# 301_FrameUSB.net
KiCad netlist of a schematic drawn in Altium Designer
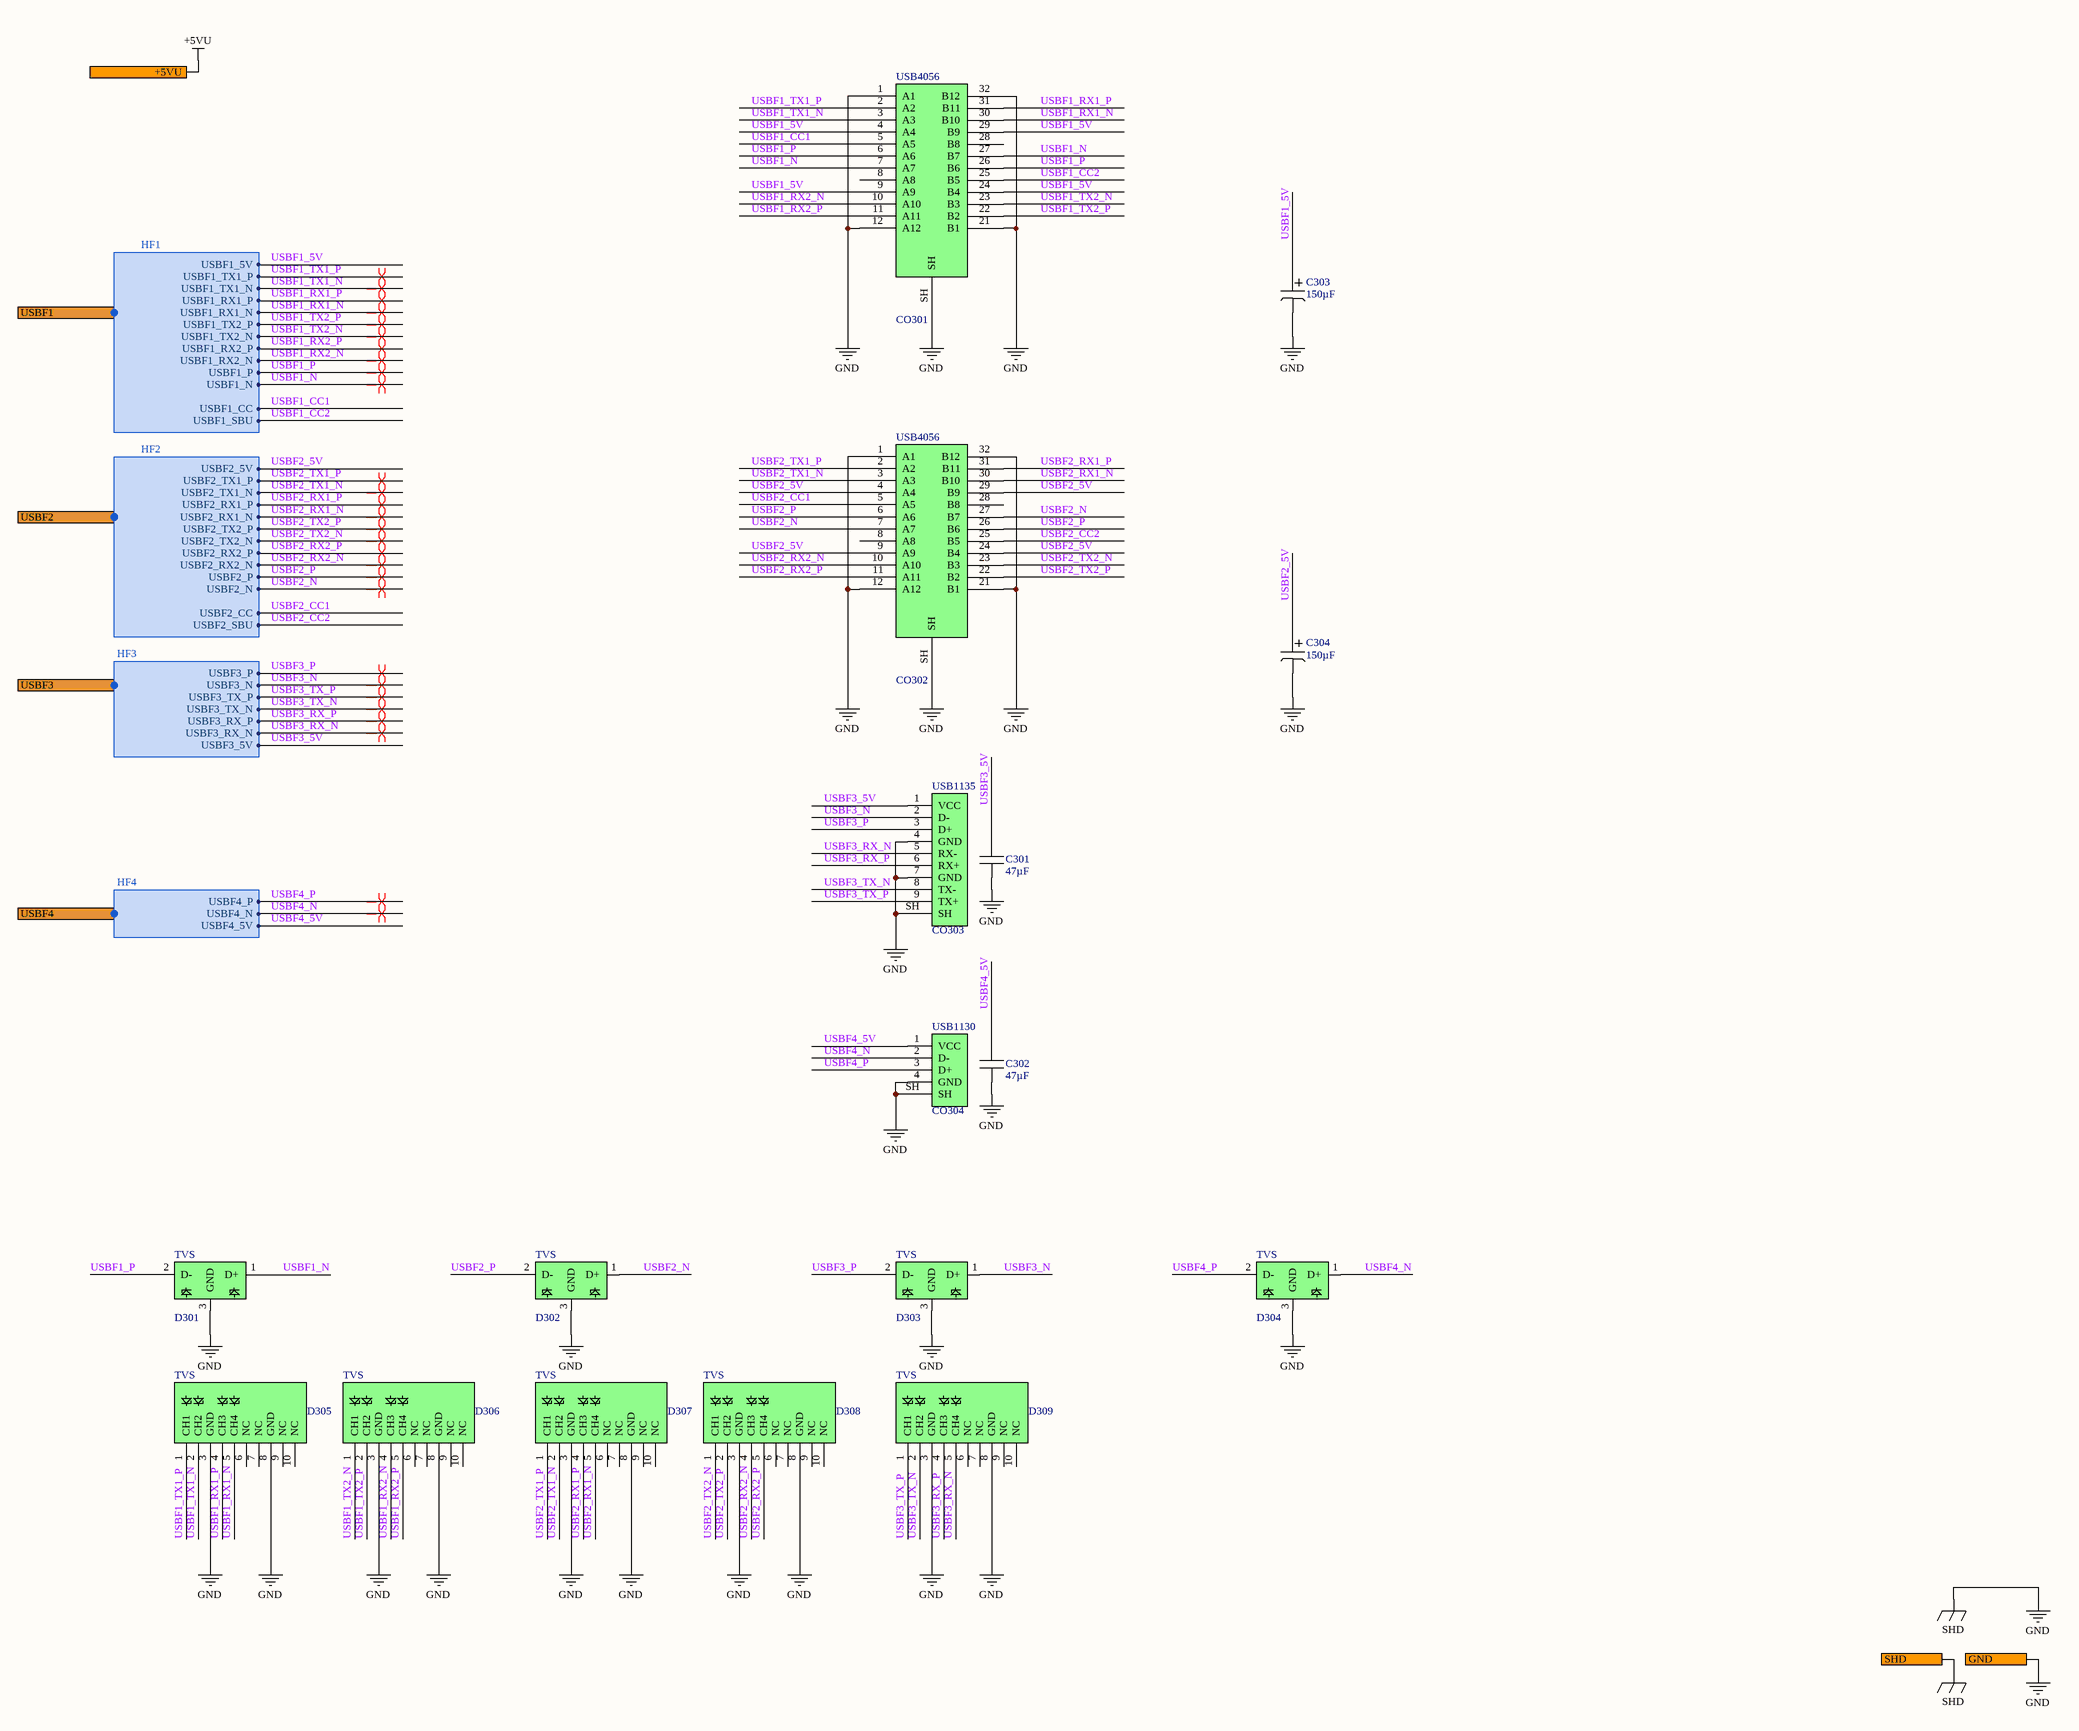
[diagram p0: 301_FrameUSB.SchDoc]

(export (version "E")
  (design (tool "Eeschema 10.0.6"))
  (components
    (comp (ref "C301")
      (value "47µF")
      (footprint "C1210")
      (description "47µF 16V 20% X5R")
      (fields
        (field (name "REFVAL") "47µF")
        (field (name "PART NUMBER") "CA0007")
        (field (name "MANFACTPART") "EMK325ABJ476MM8P")
      )
      (libsource (lib "GTS_Database") (part "C"))
    )
    (comp (ref "C302")
      (value "47µF")
      (footprint "C1210")
      (description "47µF 16V 20% X5R")
      (fields
        (field (name "REFVAL") "47µF")
        (field (name "PART NUMBER") "CA0007")
        (field (name "MANFACTPART") "EMK325ABJ476MM8P")
      )
      (libsource (lib "GTS_Database") (part "C"))
    )
    (comp (ref "C303")
      (value "150µF")
      (footprint "RL_10_5_12.5")
      (description "150µF 50V 20% 363mA")
      (fields
        (field (name "REFVAL") "150µF")
        (field (name "PART NUMBER") "CA0043")
        (field (name "MANFACTPART") "860010675016")
      )
      (libsource (lib "GTS_Database") (part "C+"))
    )
    (comp (ref "C304")
      (value "150µF")
      (footprint "RL_10_5_12.5")
      (description "150µF 50V 20% 363mA")
      (fields
        (field (name "REFVAL") "150µF")
        (field (name "PART NUMBER") "CA0043")
        (field (name "MANFACTPART") "860010675016")
      )
      (libsource (lib "GTS_Database") (part "C+"))
    )
    (comp (ref "CO301")
      (value "USB4056")
      (footprint "USB4056-03-A")
      (description "USB C connector Receptacle Horizontal")
      (fields
        (field (name "REFVAL") "USB4056")
        (field (name "PART NUMBER") "CO0030")
        (field (name "MANFACTPART") "USB4056-03-A")
      )
      (libsource (lib "GTS_Database") (part "USB-CC"))
    )
    (comp (ref "CO302")
      (value "USB4056")
      (footprint "USB4056-03-A")
      (description "USB C connector Receptacle Horizontal")
      (fields
        (field (name "REFVAL") "USB4056")
        (field (name "PART NUMBER") "CO0030")
        (field (name "MANFACTPART") "USB4056-03-A")
      )
      (libsource (lib "GTS_Database") (part "USB-CC"))
    )
    (comp (ref "CO303")
      (value "USB1135")
      (footprint "USB1135-15-9-L-B")
      (description "USB3.0 Type A receptacle Horizontal")
      (fields
        (field (name "REFVAL") "USB1135")
        (field (name "PART NUMBER") "CO0041")
        (field (name "MANFACTPART") "USB1135-15-9-L-B")
      )
      (libsource (lib "GTS_Database") (part "USB3"))
    )
    (comp (ref "CO304")
      (value "USB1130")
      (footprint "USB1130-15-A")
      (description "USB2.0 Type A receptacle Horizontal")
      (fields
        (field (name "REFVAL") "USB1130")
        (field (name "PART NUMBER") "CO0040")
        (field (name "MANFACTPART") "USB1130-15-A")
      )
      (libsource (lib "GTS_Database") (part "USB2"))
    )
    (comp (ref "D301")
      (value "TVS")
      (footprint "SOT-3")
      (description "USB 2 TVS Diode")
      (fields
        (field (name "REFVAL") "TVS")
        (field (name "PART NUMBER") "DI0002")
        (field (name "MANFACTPART") "TPD2EUSB30DRTR")
      )
      (libsource (lib "GTS_Database") (part "USB2TVS"))
    )
    (comp (ref "D302")
      (value "TVS")
      (footprint "SOT-3")
      (description "USB 2 TVS Diode")
      (fields
        (field (name "REFVAL") "TVS")
        (field (name "PART NUMBER") "DI0002")
        (field (name "MANFACTPART") "TPD2EUSB30DRTR")
      )
      (libsource (lib "GTS_Database") (part "USB2TVS"))
    )
    (comp (ref "D303")
      (value "TVS")
      (footprint "SOT-3")
      (description "USB 2 TVS Diode")
      (fields
        (field (name "REFVAL") "TVS")
        (field (name "PART NUMBER") "DI0002")
        (field (name "MANFACTPART") "TPD2EUSB30DRTR")
      )
      (libsource (lib "GTS_Database") (part "USB2TVS"))
    )
    (comp (ref "D304")
      (value "TVS")
      (footprint "SOT-3")
      (description "USB 2 TVS Diode")
      (fields
        (field (name "REFVAL") "TVS")
        (field (name "PART NUMBER") "DI0002")
        (field (name "MANFACTPART") "TPD2EUSB30DRTR")
      )
      (libsource (lib "GTS_Database") (part "USB2TVS"))
    )
    (comp (ref "D305")
      (value "TVS")
      (footprint "SOT-1176-1")
      (description "USB 3 TVS Diode")
      (fields
        (field (name "REFVAL") "TVS")
        (field (name "PART NUMBER") "DI0007")
        (field (name "MANFACTPART") "PUSB3FA2Z")
      )
      (libsource (lib "GTS_Database") (part "USB3TVS"))
    )
    (comp (ref "D306")
      (value "TVS")
      (footprint "SOT-1176-1")
      (description "USB 3 TVS Diode")
      (fields
        (field (name "REFVAL") "TVS")
        (field (name "PART NUMBER") "DI0007")
        (field (name "MANFACTPART") "PUSB3FA2Z")
      )
      (libsource (lib "GTS_Database") (part "USB3TVS"))
    )
    (comp (ref "D307")
      (value "TVS")
      (footprint "SOT-1176-1")
      (description "USB 3 TVS Diode")
      (fields
        (field (name "REFVAL") "TVS")
        (field (name "PART NUMBER") "DI0007")
        (field (name "MANFACTPART") "PUSB3FA2Z")
      )
      (libsource (lib "GTS_Database") (part "USB3TVS"))
    )
    (comp (ref "D308")
      (value "TVS")
      (footprint "SOT-1176-1")
      (description "USB 3 TVS Diode")
      (fields
        (field (name "REFVAL") "TVS")
        (field (name "PART NUMBER") "DI0007")
        (field (name "MANFACTPART") "PUSB3FA2Z")
      )
      (libsource (lib "GTS_Database") (part "USB3TVS"))
    )
    (comp (ref "D309")
      (value "TVS")
      (footprint "SOT-1176-1")
      (description "USB 3 TVS Diode")
      (fields
        (field (name "REFVAL") "TVS")
        (field (name "PART NUMBER") "DI0007")
        (field (name "MANFACTPART") "PUSB3FA2Z")
      )
      (libsource (lib "GTS_Database") (part "USB3TVS"))
    )
  )
  (nets
    (net (code "6") (name "/USBF1_5V") (class "Default")
      (node (ref "C303") (pin "1") (pinfunction "1_1") (pintype "passive"))
      (node (ref "CO301") (pin "24") (pinfunction "B4_24") (pintype "passive"))
      (node (ref "CO301") (pin "29") (pinfunction "B9_29") (pintype "passive"))
      (node (ref "CO301") (pin "4") (pinfunction "A4_4") (pintype "passive"))
      (node (ref "CO301") (pin "9") (pinfunction "A9_9") (pintype "passive"))
    )
    (net (code "7") (name "/USBF1_CC1") (class "Default")
      (node (ref "CO301") (pin "5") (pinfunction "A5_5") (pintype "passive"))
    )
    (net (code "8") (name "/USBF1_CC2") (class "Default")
      (node (ref "CO301") (pin "25") (pinfunction "B5_25") (pintype "passive"))
    )
    (net (code "9") (name "/USBF1_N") (class "Default")
      (node (ref "CO301") (pin "27") (pinfunction "B7_27") (pintype "passive"))
      (node (ref "CO301") (pin "7") (pinfunction "A7_7") (pintype "passive"))
      (node (ref "D301") (pin "1") (pinfunction "D+_1") (pintype "passive"))
    )
    (net (code "10") (name "/USBF1_P") (class "Default")
      (node (ref "CO301") (pin "26") (pinfunction "B6_26") (pintype "passive"))
      (node (ref "CO301") (pin "6") (pinfunction "A6_6") (pintype "passive"))
      (node (ref "D301") (pin "2") (pinfunction "D-_2") (pintype "passive"))
    )
    (net (code "11") (name "/USBF1_RX1_N") (class "Default")
      (node (ref "CO301") (pin "30") (pinfunction "B10_30") (pintype "passive"))
      (node (ref "D305") (pin "5") (pinfunction "CH4_5") (pintype "passive"))
    )
    (net (code "12") (name "/USBF1_RX1_P") (class "Default")
      (node (ref "CO301") (pin "31") (pinfunction "B11_31") (pintype "passive"))
      (node (ref "D305") (pin "4") (pinfunction "CH3_4") (pintype "passive"))
    )
    (net (code "13") (name "/USBF1_RX2_N") (class "Default")
      (node (ref "CO301") (pin "10") (pinfunction "A10_10") (pintype "passive"))
      (node (ref "D306") (pin "4") (pinfunction "CH3_4") (pintype "passive"))
    )
    (net (code "14") (name "/USBF1_RX2_P") (class "Default")
      (node (ref "CO301") (pin "11") (pinfunction "A11_11") (pintype "passive"))
      (node (ref "D306") (pin "5") (pinfunction "CH4_5") (pintype "passive"))
    )
    (net (code "15") (name "/USBF1_TX1_N") (class "Default")
      (node (ref "CO301") (pin "3") (pinfunction "A3_3") (pintype "passive"))
      (node (ref "D305") (pin "2") (pinfunction "CH2_2") (pintype "passive"))
    )
    (net (code "16") (name "/USBF1_TX1_P") (class "Default")
      (node (ref "CO301") (pin "2") (pinfunction "A2_2") (pintype "passive"))
      (node (ref "D305") (pin "1") (pinfunction "CH1_1") (pintype "passive"))
    )
    (net (code "17") (name "/USBF1_TX2_N") (class "Default")
      (node (ref "CO301") (pin "23") (pinfunction "B3_23") (pintype "passive"))
      (node (ref "D306") (pin "1") (pinfunction "CH1_1") (pintype "passive"))
    )
    (net (code "18") (name "/USBF1_TX2_P") (class "Default")
      (node (ref "CO301") (pin "22") (pinfunction "B2_22") (pintype "passive"))
      (node (ref "D306") (pin "2") (pinfunction "CH2_2") (pintype "passive"))
    )
    (net (code "19") (name "/USBF2_5V") (class "Default")
      (node (ref "C304") (pin "1") (pinfunction "1_1") (pintype "passive"))
      (node (ref "CO302") (pin "24") (pinfunction "B4_24") (pintype "passive"))
      (node (ref "CO302") (pin "29") (pinfunction "B9_29") (pintype "passive"))
      (node (ref "CO302") (pin "4") (pinfunction "A4_4") (pintype "passive"))
      (node (ref "CO302") (pin "9") (pinfunction "A9_9") (pintype "passive"))
    )
    (net (code "20") (name "/USBF2_CC1") (class "Default")
      (node (ref "CO302") (pin "5") (pinfunction "A5_5") (pintype "passive"))
    )
    (net (code "21") (name "/USBF2_CC2") (class "Default")
      (node (ref "CO302") (pin "25") (pinfunction "B5_25") (pintype "passive"))
    )
    (net (code "22") (name "/USBF2_N") (class "Default")
      (node (ref "CO302") (pin "27") (pinfunction "B7_27") (pintype "passive"))
      (node (ref "CO302") (pin "7") (pinfunction "A7_7") (pintype "passive"))
      (node (ref "D302") (pin "1") (pinfunction "D+_1") (pintype "passive"))
    )
    (net (code "23") (name "/USBF2_P") (class "Default")
      (node (ref "CO302") (pin "26") (pinfunction "B6_26") (pintype "passive"))
      (node (ref "CO302") (pin "6") (pinfunction "A6_6") (pintype "passive"))
      (node (ref "D302") (pin "2") (pinfunction "D-_2") (pintype "passive"))
    )
    (net (code "24") (name "/USBF2_RX1_N") (class "Default")
      (node (ref "CO302") (pin "30") (pinfunction "B10_30") (pintype "passive"))
      (node (ref "D307") (pin "5") (pinfunction "CH4_5") (pintype "passive"))
    )
    (net (code "25") (name "/USBF2_RX1_P") (class "Default")
      (node (ref "CO302") (pin "31") (pinfunction "B11_31") (pintype "passive"))
      (node (ref "D307") (pin "4") (pinfunction "CH3_4") (pintype "passive"))
    )
    (net (code "26") (name "/USBF2_RX2_N") (class "Default")
      (node (ref "CO302") (pin "10") (pinfunction "A10_10") (pintype "passive"))
      (node (ref "D308") (pin "4") (pinfunction "CH3_4") (pintype "passive"))
    )
    (net (code "27") (name "/USBF2_RX2_P") (class "Default")
      (node (ref "CO302") (pin "11") (pinfunction "A11_11") (pintype "passive"))
      (node (ref "D308") (pin "5") (pinfunction "CH4_5") (pintype "passive"))
    )
    (net (code "28") (name "/USBF2_TX1_N") (class "Default")
      (node (ref "CO302") (pin "3") (pinfunction "A3_3") (pintype "passive"))
      (node (ref "D307") (pin "2") (pinfunction "CH2_2") (pintype "passive"))
    )
    (net (code "29") (name "/USBF2_TX1_P") (class "Default")
      (node (ref "CO302") (pin "2") (pinfunction "A2_2") (pintype "passive"))
      (node (ref "D307") (pin "1") (pinfunction "CH1_1") (pintype "passive"))
    )
    (net (code "30") (name "/USBF2_TX2_N") (class "Default")
      (node (ref "CO302") (pin "23") (pinfunction "B3_23") (pintype "passive"))
      (node (ref "D308") (pin "1") (pinfunction "CH1_1") (pintype "passive"))
    )
    (net (code "31") (name "/USBF2_TX2_P") (class "Default")
      (node (ref "CO302") (pin "22") (pinfunction "B2_22") (pintype "passive"))
      (node (ref "D308") (pin "2") (pinfunction "CH2_2") (pintype "passive"))
    )
    (net (code "32") (name "/USBF3_5V") (class "Default")
      (node (ref "C301") (pin "1") (pinfunction "1_1") (pintype "passive"))
      (node (ref "CO303") (pin "1") (pinfunction "VCC_1") (pintype "passive"))
    )
    (net (code "33") (name "/USBF3_N") (class "Default")
      (node (ref "CO303") (pin "2") (pinfunction "D-_2") (pintype "passive"))
      (node (ref "D303") (pin "1") (pinfunction "D+_1") (pintype "passive"))
    )
    (net (code "34") (name "/USBF3_P") (class "Default")
      (node (ref "CO303") (pin "3") (pinfunction "D+_3") (pintype "passive"))
      (node (ref "D303") (pin "2") (pinfunction "D-_2") (pintype "passive"))
    )
    (net (code "35") (name "/USBF3_RX_N") (class "Default")
      (node (ref "CO303") (pin "5") (pinfunction "RX-_5") (pintype "passive"))
      (node (ref "D309") (pin "5") (pinfunction "CH4_5") (pintype "passive"))
    )
    (net (code "36") (name "/USBF3_RX_P") (class "Default")
      (node (ref "CO303") (pin "6") (pinfunction "RX+_6") (pintype "passive"))
      (node (ref "D309") (pin "4") (pinfunction "CH3_4") (pintype "passive"))
    )
    (net (code "37") (name "/USBF3_TX_N") (class "Default")
      (node (ref "CO303") (pin "8") (pinfunction "TX-_8") (pintype "passive"))
      (node (ref "D309") (pin "2") (pinfunction "CH2_2") (pintype "passive"))
    )
    (net (code "38") (name "/USBF3_TX_P") (class "Default")
      (node (ref "CO303") (pin "9") (pinfunction "TX+_9") (pintype "passive"))
      (node (ref "D309") (pin "1") (pinfunction "CH1_1") (pintype "passive"))
    )
    (net (code "39") (name "/USBF4_5V") (class "Default")
      (node (ref "C302") (pin "1") (pinfunction "1_1") (pintype "passive"))
      (node (ref "CO304") (pin "1") (pinfunction "VCC_1") (pintype "passive"))
    )
    (net (code "40") (name "/USBF4_N") (class "Default")
      (node (ref "CO304") (pin "2") (pinfunction "D-_2") (pintype "passive"))
      (node (ref "D304") (pin "1") (pinfunction "D+_1") (pintype "passive"))
    )
    (net (code "41") (name "/USBF4_P") (class "Default")
      (node (ref "CO304") (pin "3") (pinfunction "D+_3") (pintype "passive"))
      (node (ref "D304") (pin "2") (pinfunction "D-_2") (pintype "passive"))
    )
    (net (code "46") (name "GND") (class "Default")
      (node (ref "C301") (pin "2") (pinfunction "2_2") (pintype "passive"))
      (node (ref "C302") (pin "2") (pinfunction "2_2") (pintype "passive"))
      (node (ref "C303") (pin "2") (pinfunction "2_2") (pintype "passive"))
      (node (ref "C304") (pin "2") (pinfunction "2_2") (pintype "passive"))
      (node (ref "CO301") (pin "1") (pinfunction "A1_1") (pintype "passive"))
      (node (ref "CO301") (pin "12") (pinfunction "A12_12") (pintype "passive"))
      (node (ref "CO301") (pin "21") (pinfunction "B1_21") (pintype "passive"))
      (node (ref "CO301") (pin "32") (pinfunction "B12_32") (pintype "passive"))
      (node (ref "CO301") (pin "SH") (pinfunction "SH_SH") (pintype "power_in"))
      (node (ref "CO302") (pin "1") (pinfunction "A1_1") (pintype "passive"))
      (node (ref "CO302") (pin "12") (pinfunction "A12_12") (pintype "passive"))
      (node (ref "CO302") (pin "21") (pinfunction "B1_21") (pintype "passive"))
      (node (ref "CO302") (pin "32") (pinfunction "B12_32") (pintype "passive"))
      (node (ref "CO302") (pin "SH") (pinfunction "SH_SH") (pintype "power_in"))
      (node (ref "CO303") (pin "4") (pinfunction "GND_4") (pintype "passive"))
      (node (ref "CO303") (pin "7") (pinfunction "GND_7") (pintype "passive"))
      (node (ref "CO303") (pin "SH") (pinfunction "SH_SH") (pintype "passive"))
      (node (ref "CO304") (pin "4") (pinfunction "GND_4") (pintype "passive"))
      (node (ref "CO304") (pin "SH") (pinfunction "SH_SH") (pintype "passive"))
      (node (ref "D301") (pin "3") (pinfunction "GND_3") (pintype "power_in"))
      (node (ref "D302") (pin "3") (pinfunction "GND_3") (pintype "power_in"))
      (node (ref "D303") (pin "3") (pinfunction "GND_3") (pintype "power_in"))
      (node (ref "D304") (pin "3") (pinfunction "GND_3") (pintype "power_in"))
      (node (ref "D305") (pin "3") (pinfunction "GND_3") (pintype "passive"))
      (node (ref "D305") (pin "8") (pinfunction "GND_8") (pintype "passive"))
      (node (ref "D306") (pin "3") (pinfunction "GND_3") (pintype "passive"))
      (node (ref "D306") (pin "8") (pinfunction "GND_8") (pintype "passive"))
      (node (ref "D307") (pin "3") (pinfunction "GND_3") (pintype "passive"))
      (node (ref "D307") (pin "8") (pinfunction "GND_8") (pintype "passive"))
      (node (ref "D308") (pin "3") (pinfunction "GND_3") (pintype "passive"))
      (node (ref "D308") (pin "8") (pinfunction "GND_8") (pintype "passive"))
      (node (ref "D309") (pin "3") (pinfunction "GND_3") (pintype "passive"))
      (node (ref "D309") (pin "8") (pinfunction "GND_8") (pintype "passive"))
    )
    (net (code "47") (name "unconnected-(CO301-A8-Pad8)") (class "Default")
      (node (ref "CO301") (pin "8") (pinfunction "A8_8") (pintype "passive"))
    )
    (net (code "48") (name "unconnected-(CO301-B8-Pad28)") (class "Default")
      (node (ref "CO301") (pin "28") (pinfunction "B8_28") (pintype "passive"))
    )
    (net (code "49") (name "unconnected-(CO302-A8-Pad8)") (class "Default")
      (node (ref "CO302") (pin "8") (pinfunction "A8_8") (pintype "passive"))
    )
    (net (code "50") (name "unconnected-(CO302-B8-Pad28)") (class "Default")
      (node (ref "CO302") (pin "28") (pinfunction "B8_28") (pintype "passive"))
    )
    (net (code "51") (name "unconnected-(D305-NC-Pad6)") (class "Default")
      (node (ref "D305") (pin "6") (pinfunction "NC_6") (pintype "passive"))
    )
    (net (code "52") (name "unconnected-(D305-NC-Pad7)") (class "Default")
      (node (ref "D305") (pin "7") (pinfunction "NC_7") (pintype "passive"))
    )
    (net (code "53") (name "unconnected-(D305-NC-Pad9)") (class "Default")
      (node (ref "D305") (pin "9") (pinfunction "NC_9") (pintype "passive"))
    )
    (net (code "54") (name "unconnected-(D305-NC-Pad10)") (class "Default")
      (node (ref "D305") (pin "10") (pinfunction "NC_10") (pintype "passive"))
    )
    (net (code "55") (name "unconnected-(D306-NC-Pad6)") (class "Default")
      (node (ref "D306") (pin "6") (pinfunction "NC_6") (pintype "passive"))
    )
    (net (code "56") (name "unconnected-(D306-NC-Pad7)") (class "Default")
      (node (ref "D306") (pin "7") (pinfunction "NC_7") (pintype "passive"))
    )
    (net (code "57") (name "unconnected-(D306-NC-Pad9)") (class "Default")
      (node (ref "D306") (pin "9") (pinfunction "NC_9") (pintype "passive"))
    )
    (net (code "58") (name "unconnected-(D306-NC-Pad10)") (class "Default")
      (node (ref "D306") (pin "10") (pinfunction "NC_10") (pintype "passive"))
    )
    (net (code "59") (name "unconnected-(D307-NC-Pad6)") (class "Default")
      (node (ref "D307") (pin "6") (pinfunction "NC_6") (pintype "passive"))
    )
    (net (code "60") (name "unconnected-(D307-NC-Pad7)") (class "Default")
      (node (ref "D307") (pin "7") (pinfunction "NC_7") (pintype "passive"))
    )
    (net (code "61") (name "unconnected-(D307-NC-Pad9)") (class "Default")
      (node (ref "D307") (pin "9") (pinfunction "NC_9") (pintype "passive"))
    )
    (net (code "62") (name "unconnected-(D307-NC-Pad10)") (class "Default")
      (node (ref "D307") (pin "10") (pinfunction "NC_10") (pintype "passive"))
    )
    (net (code "63") (name "unconnected-(D308-NC-Pad6)") (class "Default")
      (node (ref "D308") (pin "6") (pinfunction "NC_6") (pintype "passive"))
    )
    (net (code "64") (name "unconnected-(D308-NC-Pad7)") (class "Default")
      (node (ref "D308") (pin "7") (pinfunction "NC_7") (pintype "passive"))
    )
    (net (code "65") (name "unconnected-(D308-NC-Pad9)") (class "Default")
      (node (ref "D308") (pin "9") (pinfunction "NC_9") (pintype "passive"))
    )
    (net (code "66") (name "unconnected-(D308-NC-Pad10)") (class "Default")
      (node (ref "D308") (pin "10") (pinfunction "NC_10") (pintype "passive"))
    )
    (net (code "67") (name "unconnected-(D309-NC-Pad6)") (class "Default")
      (node (ref "D309") (pin "6") (pinfunction "NC_6") (pintype "passive"))
    )
    (net (code "68") (name "unconnected-(D309-NC-Pad7)") (class "Default")
      (node (ref "D309") (pin "7") (pinfunction "NC_7") (pintype "passive"))
    )
    (net (code "69") (name "unconnected-(D309-NC-Pad9)") (class "Default")
      (node (ref "D309") (pin "9") (pinfunction "NC_9") (pintype "passive"))
    )
    (net (code "70") (name "unconnected-(D309-NC-Pad10)") (class "Default")
      (node (ref "D309") (pin "10") (pinfunction "NC_10") (pintype "passive"))
    )
  )
)
